# a.net
KiCad netlist of a schematic drawn in EAGLE
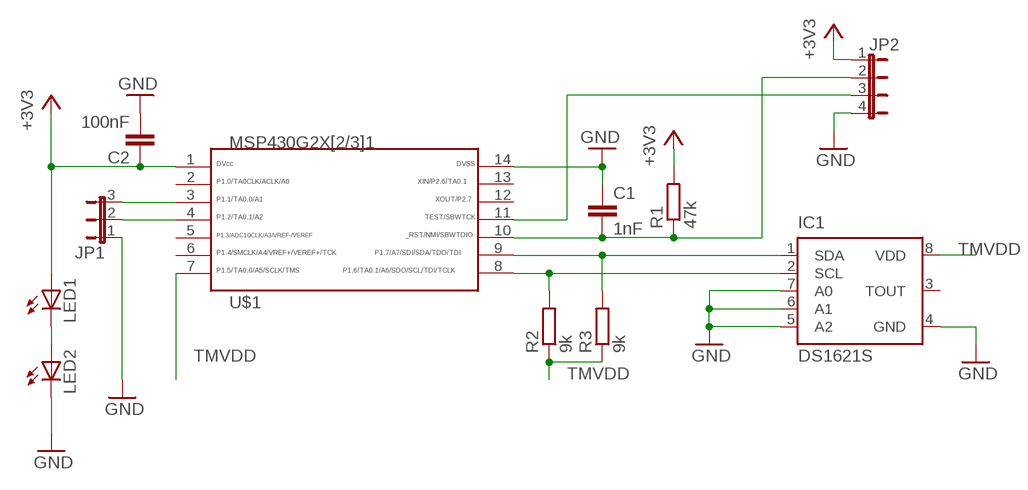
[diagram p0: schematic, sheet 1]

(export (version "E")
  (design (tool "Eeschema 10.0.6"))
  (components
    (comp (ref "C1")
      (value "1nF")
      (footprint "eagle-import:C0603K")
      (libsource (lib "eagle-import") (part "C-EUC0603K"))
    )
    (comp (ref "C2")
      (value "100nF")
      (footprint "eagle-import:C1206K")
      (libsource (lib "eagle-import") (part "C-EUC1206K"))
    )
    (comp (ref "IC1")
      (value "DS1621S")
      (footprint "eagle-import:SO08")
      (fields (field (name "MF") "DALLAS SEMICONDUCTOR") (field (name "MPN") "DS1621S+"))
      (libsource (lib "eagle-import") (part "DS1621S"))
    )
    (comp (ref "JP1")
      (value "JP2E")
      (footprint "eagle-import:JP2")
      (libsource (lib "eagle-import") (part "JP2E"))
    )
    (comp (ref "JP2")
      (value "JP4E")
      (footprint "eagle-import:JP4")
      (libsource (lib "eagle-import") (part "JP4E"))
    )
    (comp (ref "LED1")
      (value "LED3MM")
      (footprint "eagle-import:LED3MM")
      (libsource (lib "eagle-import") (part "LED3MM"))
    )
    (comp (ref "LED2")
      (value "LED3MM")
      (footprint "eagle-import:LED3MM")
      (libsource (lib "eagle-import") (part "LED3MM"))
    )
    (comp (ref "R1")
      (value "47k")
      (footprint "eagle-import:R1206")
      (libsource (lib "eagle-import") (part "R-EU_R1206"))
    )
    (comp (ref "R2")
      (value "9k")
      (footprint "eagle-import:M0805")
      (libsource (lib "eagle-import") (part "R-EU_M0805"))
    )
    (comp (ref "R3")
      (value "9k")
      (footprint "eagle-import:M0805")
      (libsource (lib "eagle-import") (part "R-EU_M0805"))
    )
    (comp (ref "U$1")
      (value "G2X[2/3]1---PW14")
      (footprint "eagle-import:PW14")
      (libsource (lib "eagle-import") (part "G2X[2/3]1---PW14"))
    )
  )
  (nets
    (net (code "1") (name "+3V3") (class "Default")
      (node (ref "C2") (pin "1") (pinfunction "1_1") (pintype "passive"))
      (node (ref "JP2") (pin "1") (pinfunction "1_1") (pintype "passive"))
      (node (ref "LED1") (pin "A") (pinfunction "A_A") (pintype "passive"))
      (node (ref "R1") (pin "2") (pinfunction "2_2") (pintype "passive"))
      (node (ref "U$1") (pin "1") (pinfunction "1_1") (pintype "bidirectional"))
    )
    (net (code "2") (name "/TMVDD") (class "Default")
      (node (ref "IC1") (pin "8") (pinfunction "VDD_8") (pintype "power_in"))
      (node (ref "R2") (pin "1") (pinfunction "1_1") (pintype "passive"))
      (node (ref "R3") (pin "1") (pinfunction "1_1") (pintype "passive"))
      (node (ref "U$1") (pin "7") (pinfunction "7_7") (pintype "bidirectional"))
    )
    (net (code "3") (name "GND") (class "Default")
      (node (ref "C1") (pin "1") (pinfunction "1_1") (pintype "passive"))
      (node (ref "C2") (pin "2") (pinfunction "2_2") (pintype "passive"))
      (node (ref "IC1") (pin "4") (pinfunction "GND_4") (pintype "power_in"))
      (node (ref "IC1") (pin "5") (pinfunction "A2_5") (pintype "input"))
      (node (ref "IC1") (pin "6") (pinfunction "A1_6") (pintype "input"))
      (node (ref "IC1") (pin "7") (pinfunction "A0_7") (pintype "input"))
      (node (ref "JP1") (pin "1") (pinfunction "1_1") (pintype "passive"))
      (node (ref "JP2") (pin "4") (pinfunction "4_4") (pintype "passive"))
      (node (ref "LED2") (pin "K") (pinfunction "C_K") (pintype "passive"))
      (node (ref "U$1") (pin "14") (pinfunction "14_14") (pintype "bidirectional"))
    )
    (net (code "4") (name "Net-(C1-Pad2)") (class "Default")
      (node (ref "C1") (pin "2") (pinfunction "2_2") (pintype "passive"))
      (node (ref "JP2") (pin "2") (pinfunction "2_2") (pintype "passive"))
      (node (ref "R1") (pin "1") (pinfunction "1_1") (pintype "passive"))
      (node (ref "U$1") (pin "10") (pinfunction "10_10") (pintype "bidirectional"))
    )
    (net (code "5") (name "Net-(IC1-SCL)") (class "Default")
      (node (ref "IC1") (pin "2") (pinfunction "SCL_2") (pintype "input"))
      (node (ref "R2") (pin "2") (pinfunction "2_2") (pintype "passive"))
      (node (ref "U$1") (pin "8") (pinfunction "8_8") (pintype "bidirectional"))
    )
    (net (code "6") (name "Net-(IC1-SDA)") (class "Default")
      (node (ref "IC1") (pin "1") (pinfunction "SDA_1") (pintype "bidirectional"))
      (node (ref "R3") (pin "2") (pinfunction "2_2") (pintype "passive"))
      (node (ref "U$1") (pin "9") (pinfunction "9_9") (pintype "bidirectional"))
    )
    (net (code "7") (name "Net-(JP1-Pad2)") (class "Default")
      (node (ref "JP1") (pin "2") (pinfunction "2_2") (pintype "passive"))
      (node (ref "U$1") (pin "4") (pinfunction "4_4") (pintype "bidirectional"))
    )
    (net (code "8") (name "Net-(JP1-Pad3)") (class "Default")
      (node (ref "JP1") (pin "3") (pinfunction "3_3") (pintype "passive"))
      (node (ref "U$1") (pin "3") (pinfunction "3_3") (pintype "bidirectional"))
    )
    (net (code "9") (name "Net-(JP2-Pad3)") (class "Default")
      (node (ref "JP2") (pin "3") (pinfunction "3_3") (pintype "passive"))
      (node (ref "U$1") (pin "11") (pinfunction "11_11") (pintype "bidirectional"))
    )
    (net (code "10") (name "Net-(LED1-C)") (class "Default")
      (node (ref "LED1") (pin "K") (pinfunction "C_K") (pintype "passive"))
      (node (ref "LED2") (pin "A") (pinfunction "A_A") (pintype "passive"))
    )
    (net (code "11") (name "unconnected-(IC1-TOUT-Pad3)") (class "Default")
      (node (ref "IC1") (pin "3") (pinfunction "TOUT_3") (pintype "output"))
    )
    (net (code "12") (name "unconnected-(U$1-Pad2)") (class "Default")
      (node (ref "U$1") (pin "2") (pinfunction "2_2") (pintype "bidirectional"))
    )
    (net (code "13") (name "unconnected-(U$1-Pad5)") (class "Default")
      (node (ref "U$1") (pin "5") (pinfunction "5_5") (pintype "bidirectional"))
    )
    (net (code "14") (name "unconnected-(U$1-Pad6)") (class "Default")
      (node (ref "U$1") (pin "6") (pinfunction "6_6") (pintype "bidirectional"))
    )
    (net (code "15") (name "unconnected-(U$1-Pad12)") (class "Default")
      (node (ref "U$1") (pin "12") (pinfunction "12_12") (pintype "bidirectional"))
    )
    (net (code "16") (name "unconnected-(U$1-Pad13)") (class "Default")
      (node (ref "U$1") (pin "13") (pinfunction "13_13") (pintype "bidirectional"))
    )
  )
)
